# OpenChill_Main_Board.net
KiCad netlist of a schematic drawn in Altium Designer
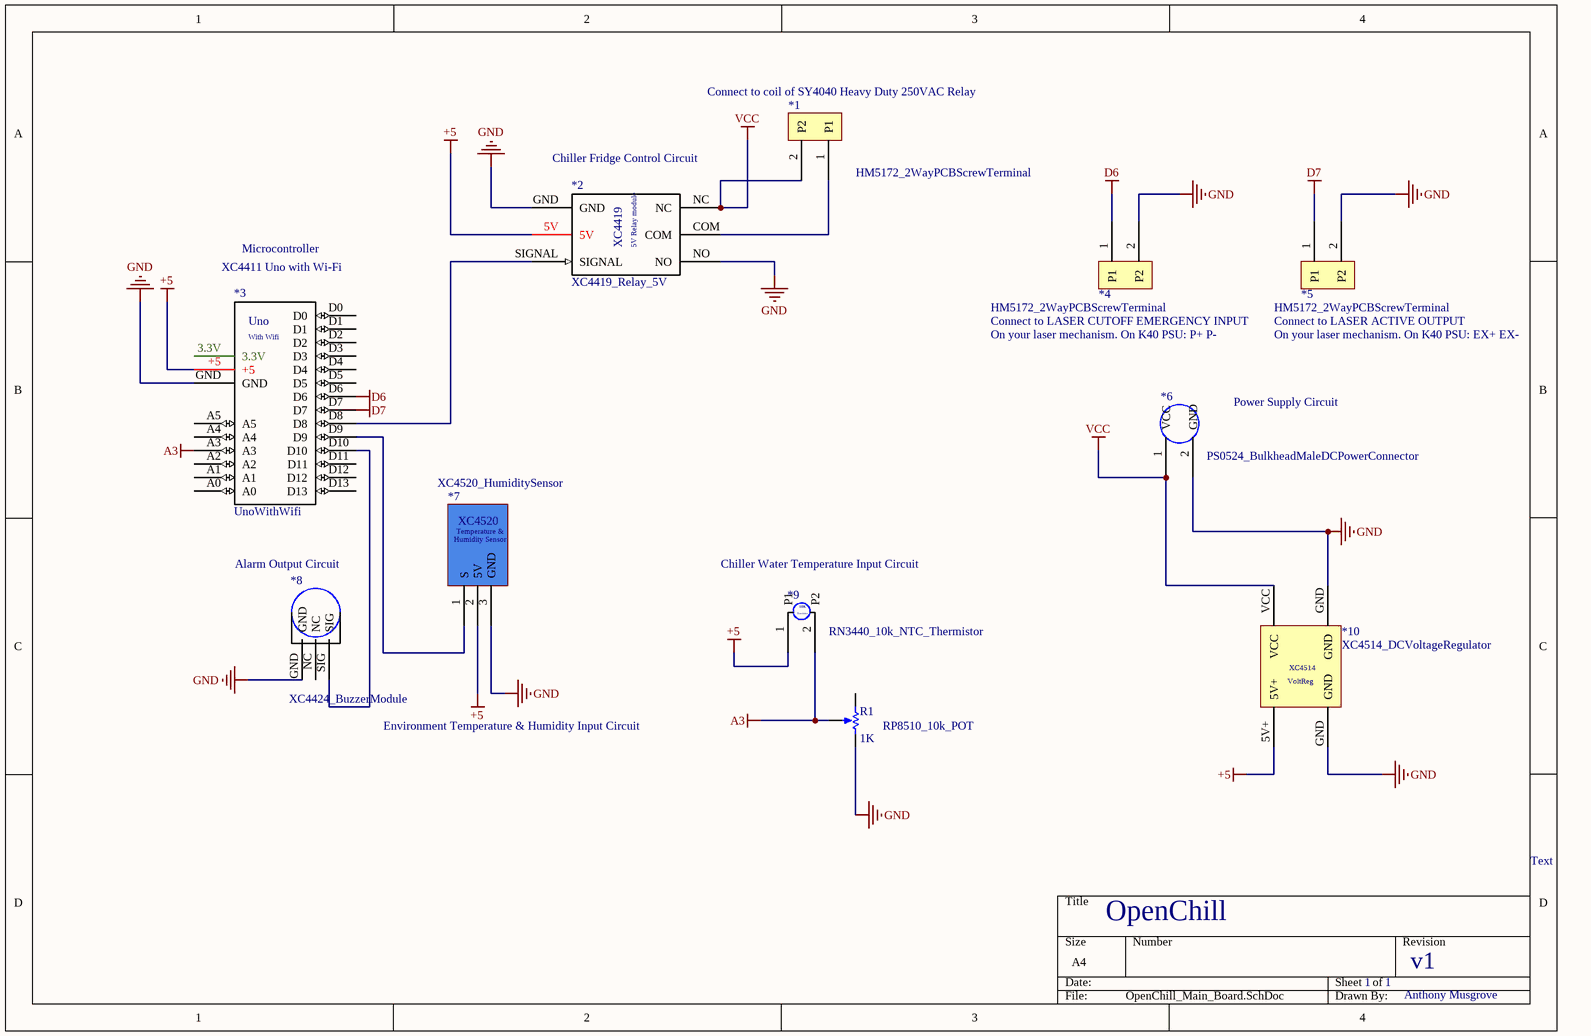
[diagram p0: OpenChill_Main_Board.SchDoc]

(export (version "E")
  (design (tool "Eeschema 10.0.6"))
  (components
    (comp (ref "*1")
      (value "HM5172_2WayPCBScrewTerminal")
      (footprint "OpenChill_2xThruHole")
      (libsource (lib "") (part "HM5172_2WayPCBScrewTerminal_1"))
    )
    (comp (ref "*2")
      (value "XC4419_Relay_5V")
      (footprint "XC4419_5VRelay_Footprint")
      (libsource (lib "OpenChill_Components_Library") (part "XC4419_Relay_5V"))
    )
    (comp (ref "*3")
      (value "UnoWithWifi")
      (footprint "ARDUINO_INTERFACE_FOOTPRINT")
      (libsource (lib "OpenChill_Components_Library") (part "UnoWithWifi"))
    )
    (comp (ref "*4")
      (value "HM5172_2WayPCBScrewTerminal")
      (footprint "OpenChill_2xThruHole")
      (description "LASER CUTOFF EMERGENCY")
      (libsource (lib "OpenChill_Components_Library") (part "HM5172_2WayPCBScrewTerminal"))
    )
    (comp (ref "*5")
      (value "HM5172_2WayPCBScrewTerminal")
      (footprint "OpenChill_2xThruHole")
      (description "LASER ACTIVE")
      (libsource (lib "OpenChill_Components_Library") (part "HM5172_2WayPCBScrewTerminal"))
    )
    (comp (ref "*6")
      (value "PS0524_BulkheadMaleDCPowerConnector")
      (footprint "OpenChill_2xThruHole")
      (libsource (lib "OpenChill_Components_Library") (part "PS0524_BulkheadMaleDCPowerConnector"))
    )
    (comp (ref "*7")
      (value "XC4520_HumiditySensor")
      (footprint "OpenChill_3xThruHole")
      (libsource (lib "OpenChill_Components_Library") (part "XC4520_HumiditySensor"))
    )
    (comp (ref "*8")
      (value "XC4424_BuzzerModule")
      (footprint "XC4424_BuzzerModule_Footprint")
      (libsource (lib "OpenChill_Components_Library") (part "XC4424_BuzzerModule"))
    )
    (comp (ref "*9")
      (value "RN3440_10k_NTC_Thermistor")
      (footprint "OpenChill_2xThruHole")
      (libsource (lib "OpenChill_Components_Library") (part "RN3440_10k_NTC_Thermistor"))
    )
    (comp (ref "*10")
      (value "XC4514_DCVoltageRegulator")
      (footprint "XC4514_VoltReg_Footprint")
      (libsource (lib "OpenChill_Components_Library") (part "XC4514_DCVoltageRegulator"))
    )
    (comp (ref "R1")
      (value "RP8510_10k_POT")
      (footprint "VR5")
      (description "Potentiometer")
      (fields (field (name "ALTIUM_VALUE") "1K") (field (name "PUBLISHER") "Altium Limited"))
      (libsource (lib "Miscellaneous Devices") (part "RPot"))
    )
  )
  (nets
    (net (code "1") (name "+5") (class "Default")
      (node (ref "*10") (pin "5V+") (pinfunction "5V+_5V+") (pintype "power_in"))
      (node (ref "*2") (pin "5V") (pinfunction "5V_5V") (pintype "power_in"))
      (node (ref "*3") (pin "+5") (pinfunction "+5_+5") (pintype "power_in"))
      (node (ref "*7") (pin "2") (pinfunction "5V_2") (pintype "passive"))
      (node (ref "*9") (pin "1") (pinfunction "P1_1") (pintype "passive"))
    )
    (net (code "2") (name "A3") (class "Default")
      (node (ref "*3") (pin "A3") (pinfunction "A3_A3") (pintype "bidirectional"))
      (node (ref "*9") (pin "2") (pinfunction "P2_2") (pintype "passive"))
      (node (ref "R1") (pin "3") (pinfunction "TAP_3") (pintype "passive"))
    )
    (net (code "3") (name "D6") (class "Default")
      (node (ref "*3") (pin "D6") (pinfunction "D6_D6") (pintype "bidirectional"))
      (node (ref "*4") (pin "1") (pinfunction "P1_1") (pintype "passive"))
    )
    (net (code "4") (name "D7") (class "Default")
      (node (ref "*3") (pin "D7") (pinfunction "D7_D7") (pintype "bidirectional"))
      (node (ref "*5") (pin "1") (pinfunction "P1_1") (pintype "passive"))
    )
    (net (code "5") (name "GND") (class "Default")
      (node (ref "*10") (pin "GND") (pinfunction "GND_GND") (pintype "power_in"))
      (node (ref "*2") (pin "GND") (pinfunction "GND_GND") (pintype "power_in"))
      (node (ref "*2") (pin "NO") (pinfunction "NO_NO") (pintype "passive"))
      (node (ref "*3") (pin "GND") (pinfunction "GND_GND") (pintype "power_in"))
      (node (ref "*4") (pin "2") (pinfunction "P2_2") (pintype "passive"))
      (node (ref "*5") (pin "2") (pinfunction "P2_2") (pintype "passive"))
      (node (ref "*6") (pin "2") (pinfunction "GND_2") (pintype "power_in"))
      (node (ref "*7") (pin "3") (pinfunction "GND_3") (pintype "passive"))
      (node (ref "*8") (pin "GND") (pinfunction "GND_GND") (pintype "passive"))
      (node (ref "R1") (pin "2") (pinfunction "BOT_2") (pintype "passive"))
    )
    (net (code "6") (name "Net-(*1-P1)") (class "Default")
      (node (ref "*1") (pin "1") (pinfunction "P1_1") (pintype "passive"))
      (node (ref "*2") (pin "COM") (pinfunction "COM_COM") (pintype "passive"))
    )
    (net (code "7") (name "Net-(*2-PadSIGNAL)") (class "Default")
      (node (ref "*2") (pin "SIGNAL") (pinfunction "SIGNAL_SIGNAL") (pintype "input"))
      (node (ref "*3") (pin "D8") (pinfunction "D8_D8") (pintype "bidirectional"))
    )
    (net (code "8") (name "Net-(*3-PadD10)") (class "Default")
      (node (ref "*3") (pin "D10") (pinfunction "D10_D10") (pintype "bidirectional"))
      (node (ref "*8") (pin "SIG") (pinfunction "SIG_SIG") (pintype "passive"))
    )
    (net (code "9") (name "Net-(*7-S)") (class "Default")
      (node (ref "*3") (pin "D9") (pinfunction "D9_D9") (pintype "bidirectional"))
      (node (ref "*7") (pin "1") (pinfunction "S_1") (pintype "passive"))
    )
    (net (code "10") (name "VCC") (class "Default")
      (node (ref "*1") (pin "2") (pinfunction "P2_2") (pintype "passive"))
      (node (ref "*10") (pin "VCC") (pinfunction "VCC_VCC") (pintype "power_in"))
      (node (ref "*2") (pin "NC") (pinfunction "NC_NC") (pintype "passive"))
      (node (ref "*6") (pin "1") (pinfunction "VCC_1") (pintype "power_in"))
    )
    (net (code "11") (name "unconnected-(*3-Pad3.3V)") (class "Default")
      (node (ref "*3") (pin "3.3V") (pinfunction "3.3V_3.3V") (pintype "power_in"))
    )
    (net (code "12") (name "unconnected-(*3-PadA0)") (class "Default")
      (node (ref "*3") (pin "A0") (pinfunction "A0_A0") (pintype "bidirectional"))
    )
    (net (code "13") (name "unconnected-(*3-PadA1)") (class "Default")
      (node (ref "*3") (pin "A1") (pinfunction "A1_A1") (pintype "bidirectional"))
    )
    (net (code "14") (name "unconnected-(*3-PadA2)") (class "Default")
      (node (ref "*3") (pin "A2") (pinfunction "A2_A2") (pintype "bidirectional"))
    )
    (net (code "15") (name "unconnected-(*3-PadA4)") (class "Default")
      (node (ref "*3") (pin "A4") (pinfunction "A4_A4") (pintype "bidirectional"))
    )
    (net (code "16") (name "unconnected-(*3-PadA5)") (class "Default")
      (node (ref "*3") (pin "A5") (pinfunction "A5_A5") (pintype "bidirectional"))
    )
    (net (code "17") (name "unconnected-(*3-PadD0)") (class "Default")
      (node (ref "*3") (pin "D0") (pinfunction "D0_D0") (pintype "bidirectional"))
    )
    (net (code "18") (name "unconnected-(*3-PadD1)") (class "Default")
      (node (ref "*3") (pin "D1") (pinfunction "D1_D1") (pintype "bidirectional"))
    )
    (net (code "19") (name "unconnected-(*3-PadD2)") (class "Default")
      (node (ref "*3") (pin "D2") (pinfunction "D2_D2") (pintype "bidirectional"))
    )
    (net (code "20") (name "unconnected-(*3-PadD3)") (class "Default")
      (node (ref "*3") (pin "D3") (pinfunction "D3_D3") (pintype "bidirectional"))
    )
    (net (code "21") (name "unconnected-(*3-PadD4)") (class "Default")
      (node (ref "*3") (pin "D4") (pinfunction "D4_D4") (pintype "bidirectional"))
    )
    (net (code "22") (name "unconnected-(*3-PadD5)") (class "Default")
      (node (ref "*3") (pin "D5") (pinfunction "D5_D5") (pintype "bidirectional"))
    )
    (net (code "23") (name "unconnected-(*3-PadD11)") (class "Default")
      (node (ref "*3") (pin "D11") (pinfunction "D11_D11") (pintype "bidirectional"))
    )
    (net (code "24") (name "unconnected-(*3-PadD12)") (class "Default")
      (node (ref "*3") (pin "D12") (pinfunction "D12_D12") (pintype "bidirectional"))
    )
    (net (code "25") (name "unconnected-(*3-PadD13)") (class "Default")
      (node (ref "*3") (pin "D13") (pinfunction "D13_D13") (pintype "bidirectional"))
    )
    (net (code "26") (name "unconnected-(*8-PadNC)") (class "Default")
      (node (ref "*8") (pin "NC") (pinfunction "NC_NC") (pintype "passive"))
    )
    (net (code "27") (name "unconnected-(R1-TOP-Pad1)") (class "Default")
      (node (ref "R1") (pin "1") (pinfunction "TOP_1") (pintype "passive"))
    )
  )
)
